# flexpcbcableschematic.net
KiCad netlist of a schematic drawn in EasyEDA Pro
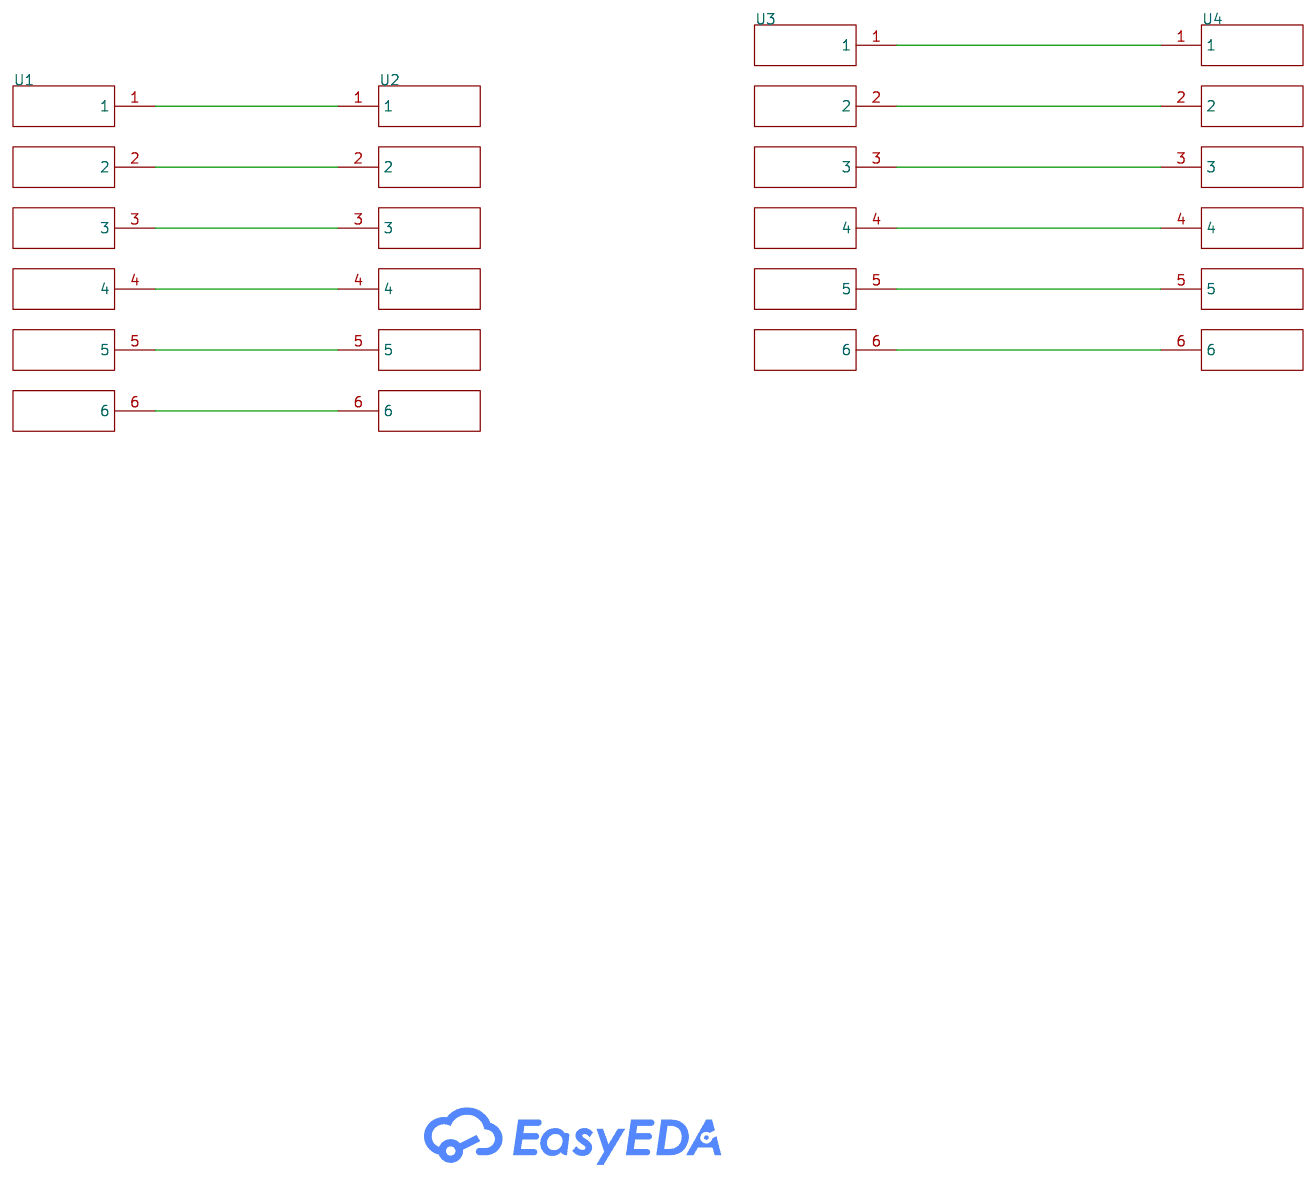
[diagram p0: schematic sheet]

(export (version "E")
  (design (tool "Eeschema 10.0.6"))
  (components
    (comp (ref "U1")
      (value "~")
      (footprint "easyedapro:6pinpadtopffc")
      (libsource (lib "easyedapro") (part "6pinpadtopffc"))
    )
    (comp (ref "U2")
      (value "~")
      (footprint "easyedapro:6pinpadtopffc")
      (libsource (lib "easyedapro") (part "6pinpadtopffc"))
    )
    (comp (ref "U3")
      (value "~")
      (footprint "easyedapro:6pinpadtopffc")
      (libsource (lib "easyedapro") (part "6pinpadtopffc"))
    )
    (comp (ref "U4")
      (value "~")
      (footprint "easyedapro:6pinpadtopffc")
      (libsource (lib "easyedapro") (part "6pinpadtopffc"))
    )
  )
  (nets
    (net (code "1") (name "Net-(U1-Pad1)") (class "Default")
      (node (ref "U1") (pin "1") (pinfunction "1_1") (pintype "input"))
      (node (ref "U2") (pin "1") (pinfunction "1_1") (pintype "input"))
    )
    (net (code "2") (name "Net-(U1-Pad2)") (class "Default")
      (node (ref "U1") (pin "2") (pinfunction "2_2") (pintype "input"))
      (node (ref "U2") (pin "2") (pinfunction "2_2") (pintype "input"))
    )
    (net (code "3") (name "Net-(U1-Pad3)") (class "Default")
      (node (ref "U1") (pin "3") (pinfunction "3_3") (pintype "input"))
      (node (ref "U2") (pin "3") (pinfunction "3_3") (pintype "input"))
    )
    (net (code "4") (name "Net-(U1-Pad4)") (class "Default")
      (node (ref "U1") (pin "4") (pinfunction "4_4") (pintype "input"))
      (node (ref "U2") (pin "4") (pinfunction "4_4") (pintype "input"))
    )
    (net (code "5") (name "Net-(U1-Pad5)") (class "Default")
      (node (ref "U1") (pin "5") (pinfunction "5_5") (pintype "input"))
      (node (ref "U2") (pin "5") (pinfunction "5_5") (pintype "input"))
    )
    (net (code "6") (name "Net-(U1-Pad6)") (class "Default")
      (node (ref "U1") (pin "6") (pinfunction "6_6") (pintype "input"))
      (node (ref "U2") (pin "6") (pinfunction "6_6") (pintype "input"))
    )
    (net (code "7") (name "Net-(U3-Pad1)") (class "Default")
      (node (ref "U3") (pin "1") (pinfunction "1_1") (pintype "input"))
      (node (ref "U4") (pin "1") (pinfunction "1_1") (pintype "input"))
    )
    (net (code "8") (name "Net-(U3-Pad2)") (class "Default")
      (node (ref "U3") (pin "2") (pinfunction "2_2") (pintype "input"))
      (node (ref "U4") (pin "2") (pinfunction "2_2") (pintype "input"))
    )
    (net (code "9") (name "Net-(U3-Pad3)") (class "Default")
      (node (ref "U3") (pin "3") (pinfunction "3_3") (pintype "input"))
      (node (ref "U4") (pin "3") (pinfunction "3_3") (pintype "input"))
    )
    (net (code "10") (name "Net-(U3-Pad4)") (class "Default")
      (node (ref "U3") (pin "4") (pinfunction "4_4") (pintype "input"))
      (node (ref "U4") (pin "4") (pinfunction "4_4") (pintype "input"))
    )
    (net (code "11") (name "Net-(U3-Pad5)") (class "Default")
      (node (ref "U3") (pin "5") (pinfunction "5_5") (pintype "input"))
      (node (ref "U4") (pin "5") (pinfunction "5_5") (pintype "input"))
    )
    (net (code "12") (name "Net-(U3-Pad6)") (class "Default")
      (node (ref "U3") (pin "6") (pinfunction "6_6") (pintype "input"))
      (node (ref "U4") (pin "6") (pinfunction "6_6") (pintype "input"))
    )
  )
)
